# shematic.net
KiCad netlist of a schematic drawn in EAGLE
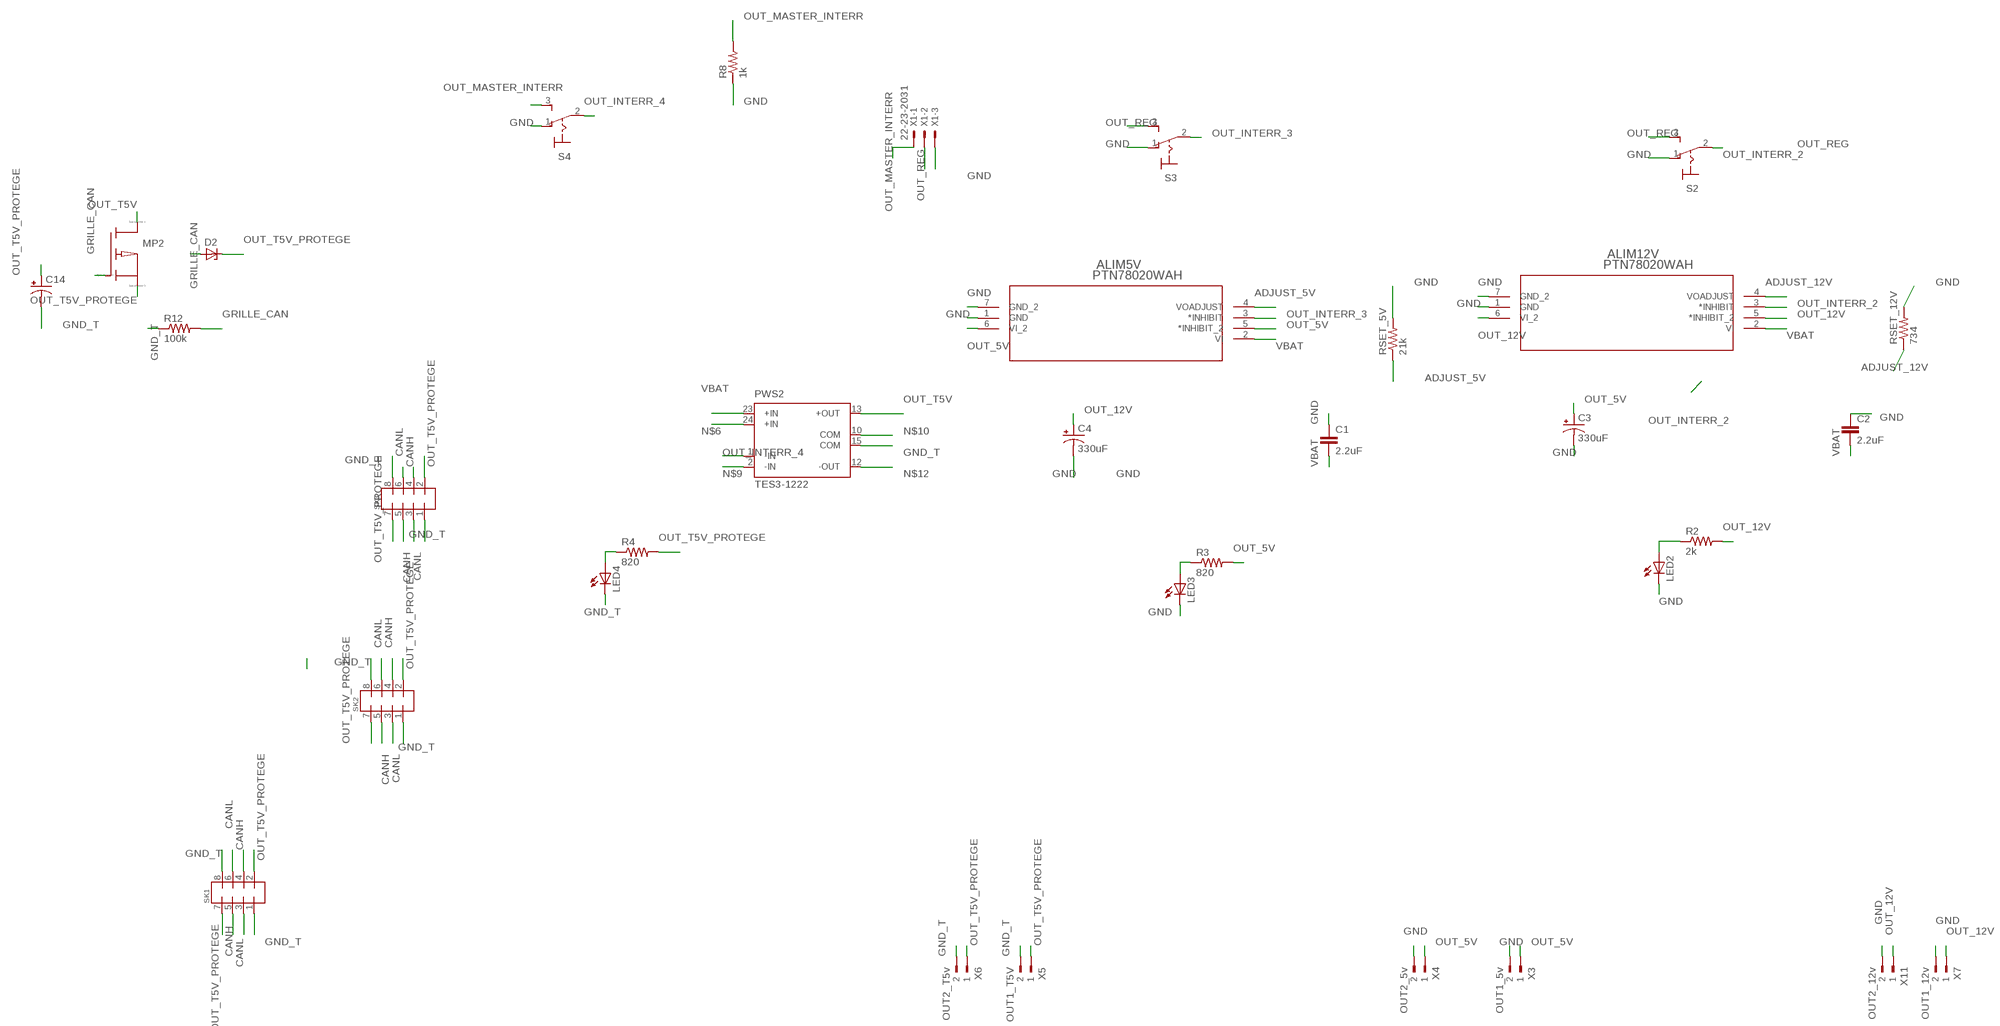
[diagram p0: schematic, sheet 1, part 1 of 2]
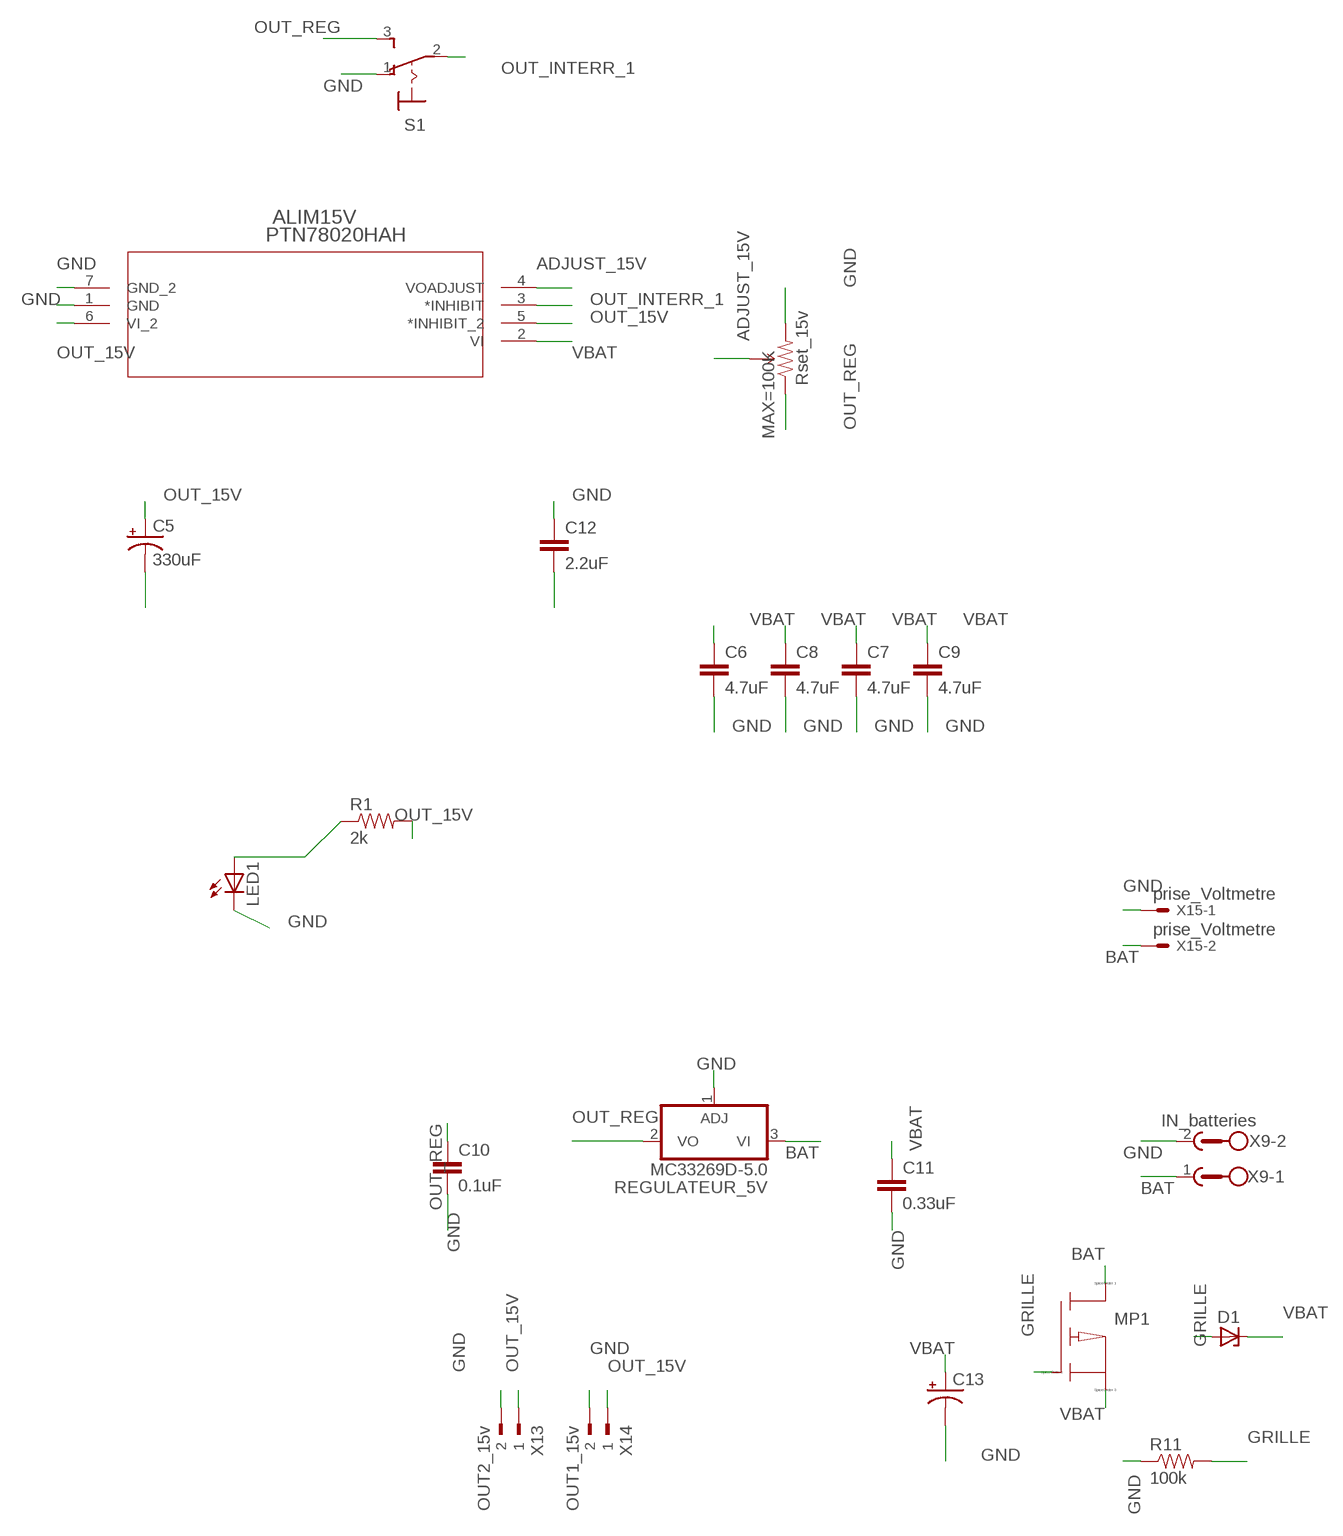
[diagram p1: schematic, sheet 1, part 2 of 2]

(export (version "E")
  (design (tool "Eeschema 10.0.6"))
  (components
    (comp (ref "ALIM5V")
      (value "PTN78020WAH")
      (footprint "eagle-import:EUK7")
      (libsource (lib "eagle-import") (part "PTN78020_"))
    )
    (comp (ref "ALIM12V")
      (value "PTN78020WAH")
      (footprint "eagle-import:EUK7")
      (libsource (lib "eagle-import") (part "PTN78020_"))
    )
    (comp (ref "ALIM15V")
      (value "PTN78020HAH")
      (footprint "eagle-import:EUK7")
      (libsource (lib "eagle-import") (part "PTN78020_"))
    )
    (comp (ref "C1")
      (value "2.2uF")
      (footprint "eagle-import:0805")
      (libsource (lib "eagle-import") (part "CAP0805"))
    )
    (comp (ref "C2")
      (value "2.2uF")
      (footprint "eagle-import:0805")
      (libsource (lib "eagle-import") (part "CAP0805"))
    )
    (comp (ref "C3")
      (value "330uF")
      (footprint "eagle-import:CPOL-RADIAL-100UF-25V")
      (libsource (lib "eagle-import") (part "CAP_POLPTH1"))
    )
    (comp (ref "C4")
      (value "330uF")
      (footprint "eagle-import:CPOL-RADIAL-100UF-25V")
      (libsource (lib "eagle-import") (part "CAP_POLPTH1"))
    )
    (comp (ref "C5")
      (value "330uF")
      (footprint "eagle-import:CPOL-RADIAL-100UF-25V")
      (libsource (lib "eagle-import") (part "CAP_POLPTH1"))
    )
    (comp (ref "C6")
      (value "4.7uF")
      (footprint "eagle-import:0805")
      (libsource (lib "eagle-import") (part "CAP0805"))
    )
    (comp (ref "C7")
      (value "4.7uF")
      (footprint "eagle-import:0805")
      (libsource (lib "eagle-import") (part "CAP0805"))
    )
    (comp (ref "C8")
      (value "4.7uF")
      (footprint "eagle-import:0805")
      (libsource (lib "eagle-import") (part "CAP0805"))
    )
    (comp (ref "C9")
      (value "4.7uF")
      (footprint "eagle-import:0805")
      (libsource (lib "eagle-import") (part "CAP0805"))
    )
    (comp (ref "C10")
      (value "0.1uF")
      (footprint "eagle-import:0805")
      (libsource (lib "eagle-import") (part "CAP0805"))
    )
    (comp (ref "C11")
      (value "0.33uF")
      (footprint "eagle-import:0805")
      (libsource (lib "eagle-import") (part "CAP0805"))
    )
    (comp (ref "C12")
      (value "2.2uF")
      (footprint "eagle-import:0805")
      (libsource (lib "eagle-import") (part "CAP0805"))
    )
    (comp (ref "C13")
      (value "CAP_POLPTH1")
      (footprint "eagle-import:CPOL-RADIAL-100UF-25V")
      (libsource (lib "eagle-import") (part "SparkFun-Passives_CAP_POLPTH1"))
    )
    (comp (ref "C14")
      (value "CAP_POLPTH1")
      (footprint "eagle-import:CPOL-RADIAL-100UF-25V")
      (libsource (lib "eagle-import") (part "SparkFun-Passives_CAP_POLPTH1"))
    )
    (comp (ref "D1")
      (value "ZENER-DIODESOT23")
      (footprint "eagle-import:SOT23")
      (libsource (lib "eagle-import") (part "ZENER-DIODESOT23"))
    )
    (comp (ref "D2")
      (value "ZENER-DIODESOT23")
      (footprint "eagle-import:SOT23")
      (libsource (lib "eagle-import") (part "ZENER-DIODESOT23"))
    )
    (comp (ref "LED1")
      (value "LEDCHIP-LED0805")
      (footprint "eagle-import:CHIP-LED0805")
      (libsource (lib "eagle-import") (part "LEDCHIP-LED0805"))
    )
    (comp (ref "LED2")
      (value "LEDCHIP-LED0805")
      (footprint "eagle-import:CHIP-LED0805")
      (libsource (lib "eagle-import") (part "LEDCHIP-LED0805"))
    )
    (comp (ref "LED3")
      (value "LEDCHIP-LED0805")
      (footprint "eagle-import:CHIP-LED0805")
      (libsource (lib "eagle-import") (part "LEDCHIP-LED0805"))
    )
    (comp (ref "LED4")
      (value "LEDCHIP-LED0805")
      (footprint "eagle-import:CHIP-LED0805")
      (libsource (lib "eagle-import") (part "LEDCHIP-LED0805"))
    )
    (comp (ref "MAX=100K")
      (value "Rset_15v")
      (footprint "eagle-import:3386U")
      (libsource (lib "eagle-import") (part "TRIMPOT-PTH-KNOB"))
    )
    (comp (ref "MP1")
      (value "PMOS")
      (footprint "eagle-import:SOT23")
      (libsource (lib "eagle-import") (part "PMOS"))
    )
    (comp (ref "MP2")
      (value "PMOS")
      (footprint "eagle-import:SOT23")
      (libsource (lib "eagle-import") (part "PMOS"))
    )
    (comp (ref "PWS2")
      (value "TES3-1222")
      (footprint "eagle-import:TES3")
      (libsource (lib "eagle-import") (part "TES3-1222"))
    )
    (comp (ref "R1")
      (value "2k")
      (footprint "eagle-import:0805")
      (libsource (lib "eagle-import") (part "SparkFun-Resistors_RESISTOR0805-RES"))
    )
    (comp (ref "R2")
      (value "2k")
      (footprint "eagle-import:0805")
      (libsource (lib "eagle-import") (part "SparkFun-Resistors_RESISTOR0805-RES"))
    )
    (comp (ref "R3")
      (value "820")
      (footprint "eagle-import:0805")
      (libsource (lib "eagle-import") (part "SparkFun-Resistors_RESISTOR0805-RES"))
    )
    (comp (ref "R4")
      (value "820")
      (footprint "eagle-import:0805")
      (libsource (lib "eagle-import") (part "SparkFun-Resistors_RESISTOR0805-RES"))
    )
    (comp (ref "R8")
      (value "1k")
      (footprint "eagle-import:0805")
      (libsource (lib "eagle-import") (part "SparkFun-Resistors_RESISTOR0805-RES"))
    )
    (comp (ref "R11")
      (value "100k")
      (footprint "eagle-import:0805")
      (libsource (lib "eagle-import") (part "RESISTOR0805-RES"))
    )
    (comp (ref "R12")
      (value "100k")
      (footprint "eagle-import:0805")
      (libsource (lib "eagle-import") (part "RESISTOR0805-RES"))
    )
    (comp (ref "REGULATEUR_5V")
      (value "MC33269D-5.0")
      (footprint "eagle-import:DPACK")
      (libsource (lib "eagle-import") (part "MC33269?D-5.0"))
    )
    (comp (ref "RSET_5V")
      (value "21k")
      (footprint "eagle-import:0805")
      (libsource (lib "eagle-import") (part "RESISTOR0805-RES"))
    )
    (comp (ref "RSET_12V")
      (value "734")
      (footprint "eagle-import:0805")
      (libsource (lib "eagle-import") (part "RESISTOR0805-RES"))
    )
    (comp (ref "S1")
      (value "M9040P")
      (footprint "eagle-import:M9040P")
      (libsource (lib "eagle-import") (part "M9040P"))
    )
    (comp (ref "S2")
      (value "M9040P")
      (footprint "eagle-import:M9040P")
      (libsource (lib "eagle-import") (part "M9040P"))
    )
    (comp (ref "S3")
      (value "M9040P")
      (footprint "eagle-import:M9040P")
      (libsource (lib "eagle-import") (part "M9040P"))
    )
    (comp (ref "S4")
      (value "M9040P")
      (footprint "eagle-import:M9040P")
      (libsource (lib "eagle-import") (part "M9040P"))
    )
    (comp (ref "SK1")
      (value "MMATCH-8-PTH")
      (footprint "eagle-import:AMP-215079-8")
      (libsource (lib "eagle-import") (part "MMATCH-8-PTH"))
    )
    (comp (ref "SK2")
      (value "MMATCH-8-PTH")
      (footprint "eagle-import:AMP-215079-8")
      (libsource (lib "eagle-import") (part "MMATCH-8-PTH"))
    )
    (comp (ref "SK3")
      (value "MMATCH-8-PTH")
      (footprint "eagle-import:AMP-215079-8")
      (libsource (lib "eagle-import") (part "MMATCH-8-PTH"))
    )
    (comp (ref "X1")
      (value "22-23-2031")
      (footprint "eagle-import:22-23-2031")
      (fields (field (name "MF") "MOLEX"))
      (libsource (lib "eagle-import") (part "22-23-2031"))
    )
    (comp (ref "X3")
      (value "OUT1_5v")
      (footprint "eagle-import:90-2")
      (libsource (lib "eagle-import") (part "90-2"))
    )
    (comp (ref "X4")
      (value "OUT2_5v")
      (footprint "eagle-import:90-2")
      (libsource (lib "eagle-import") (part "90-2"))
    )
    (comp (ref "X5")
      (value "OUT1_T5V")
      (footprint "eagle-import:90-2")
      (libsource (lib "eagle-import") (part "90-2"))
    )
    (comp (ref "X6")
      (value "OUT2_T5v")
      (footprint "eagle-import:90-2")
      (libsource (lib "eagle-import") (part "90-2"))
    )
    (comp (ref "X7")
      (value "OUT1_12v")
      (footprint "eagle-import:90-2")
      (libsource (lib "eagle-import") (part "90-2"))
    )
    (comp (ref "X9")
      (value "IN_batteries")
      (footprint "eagle-import:GMSTBA2")
      (fields (field (name "MF") "FARNELL") (field (name "MPN") "1757242"))
      (libsource (lib "eagle-import") (part "GMSTBA2"))
    )
    (comp (ref "X11")
      (value "OUT2_12v")
      (footprint "eagle-import:90-2")
      (libsource (lib "eagle-import") (part "90-2"))
    )
    (comp (ref "X13")
      (value "OUT2_15v")
      (footprint "eagle-import:90-2")
      (libsource (lib "eagle-import") (part "90-2"))
    )
    (comp (ref "X14")
      (value "OUT1_15v")
      (footprint "eagle-import:90-2")
      (libsource (lib "eagle-import") (part "90-2"))
    )
    (comp (ref "X15")
      (value "prise_Voltmetre")
      (footprint "eagle-import:KK-156-2")
      (libsource (lib "eagle-import") (part "KK-156-2"))
    )
  )
  (nets
    (net (code "1") (name "/ADJUST_5V") (class "Default")
      (node (ref "ALIM5V") (pin "4") (pinfunction "VOADJUST_4") (pintype "passive"))
      (node (ref "RSET_5V") (pin "1") (pinfunction "1_1") (pintype "passive"))
    )
    (net (code "2") (name "/ADJUST_12V") (class "Default")
      (node (ref "ALIM12V") (pin "4") (pinfunction "VOADJUST_4") (pintype "passive"))
      (node (ref "RSET_12V") (pin "1") (pinfunction "1_1") (pintype "passive"))
    )
    (net (code "3") (name "/ADJUST_15V") (class "Default")
      (node (ref "ALIM15V") (pin "4") (pinfunction "VOADJUST_4") (pintype "passive"))
      (node (ref "MAX=100K") (pin "2") (pinfunction "WIPER_2") (pintype "passive"))
    )
    (net (code "4") (name "/BAT") (class "Default")
      (node (ref "MP1") (pin "3") (pinfunction "D_3") (pintype "passive"))
      (node (ref "REGULATEUR_5V") (pin "3") (pinfunction "VI_3") (pintype "input"))
      (node (ref "X15") (pin "2") (pinfunction "S_2") (pintype "passive"))
      (node (ref "X9") (pin "1") (pinfunction "1_1") (pintype "passive"))
    )
    (net (code "5") (name "/CANH") (class "Default")
      (node (ref "SK1") (pin "4") (pinfunction "4_4") (pintype "bidirectional"))
      (node (ref "SK1") (pin "5") (pinfunction "5_5") (pintype "bidirectional"))
      (node (ref "SK2") (pin "4") (pinfunction "4_4") (pintype "bidirectional"))
      (node (ref "SK2") (pin "5") (pinfunction "5_5") (pintype "bidirectional"))
      (node (ref "SK3") (pin "4") (pinfunction "4_4") (pintype "bidirectional"))
      (node (ref "SK3") (pin "5") (pinfunction "5_5") (pintype "bidirectional"))
    )
    (net (code "6") (name "/CANL") (class "Default")
      (node (ref "SK1") (pin "3") (pinfunction "3_3") (pintype "bidirectional"))
      (node (ref "SK1") (pin "6") (pinfunction "6_6") (pintype "bidirectional"))
      (node (ref "SK2") (pin "3") (pinfunction "3_3") (pintype "bidirectional"))
      (node (ref "SK2") (pin "6") (pinfunction "6_6") (pintype "bidirectional"))
      (node (ref "SK3") (pin "3") (pinfunction "3_3") (pintype "bidirectional"))
      (node (ref "SK3") (pin "6") (pinfunction "6_6") (pintype "bidirectional"))
    )
    (net (code "7") (name "/GND") (class "Default")
      (node (ref "ALIM12V") (pin "1") (pinfunction "GND_1") (pintype "passive"))
      (node (ref "ALIM12V") (pin "7") (pinfunction "GND_2_7") (pintype "passive"))
      (node (ref "ALIM15V") (pin "1") (pinfunction "GND_1") (pintype "passive"))
      (node (ref "ALIM15V") (pin "7") (pinfunction "GND_2_7") (pintype "passive"))
      (node (ref "ALIM5V") (pin "1") (pinfunction "GND_1") (pintype "passive"))
      (node (ref "ALIM5V") (pin "7") (pinfunction "GND_2_7") (pintype "passive"))
      (node (ref "C1") (pin "1") (pinfunction "1_1") (pintype "passive"))
      (node (ref "C10") (pin "2") (pinfunction "2_2") (pintype "passive"))
      (node (ref "C11") (pin "2") (pinfunction "2_2") (pintype "passive"))
      (node (ref "C12") (pin "1") (pinfunction "1_1") (pintype "passive"))
      (node (ref "C13") (pin "2") (pinfunction "-_2") (pintype "passive"))
      (node (ref "C2") (pin "1") (pinfunction "1_1") (pintype "passive"))
      (node (ref "C3") (pin "2") (pinfunction "-_2") (pintype "passive"))
      (node (ref "C4") (pin "2") (pinfunction "-_2") (pintype "passive"))
      (node (ref "C5") (pin "2") (pinfunction "-_2") (pintype "passive"))
      (node (ref "C6") (pin "2") (pinfunction "2_2") (pintype "passive"))
      (node (ref "C7") (pin "2") (pinfunction "2_2") (pintype "passive"))
      (node (ref "C8") (pin "2") (pinfunction "2_2") (pintype "passive"))
      (node (ref "C9") (pin "2") (pinfunction "2_2") (pintype "passive"))
      (node (ref "LED1") (pin "C") (pinfunction "C_C") (pintype "passive"))
      (node (ref "LED2") (pin "C") (pinfunction "C_C") (pintype "passive"))
      (node (ref "LED3") (pin "C") (pinfunction "C_C") (pintype "passive"))
      (node (ref "MAX=100K") (pin "3") (pinfunction "CW_3") (pintype "passive"))
      (node (ref "R11") (pin "1") (pinfunction "1_1") (pintype "passive"))
      (node (ref "R8") (pin "1") (pinfunction "1_1") (pintype "passive"))
      (node (ref "REGULATEUR_5V") (pin "1") (pinfunction "ADJ_1") (pintype "input"))
      (node (ref "RSET_12V") (pin "2") (pinfunction "2_2") (pintype "passive"))
      (node (ref "RSET_5V") (pin "2") (pinfunction "2_2") (pintype "passive"))
      (node (ref "S1") (pin "1") (pinfunction "O_1") (pintype "passive"))
      (node (ref "S2") (pin "1") (pinfunction "O_1") (pintype "passive"))
      (node (ref "S3") (pin "1") (pinfunction "O_1") (pintype "passive"))
      (node (ref "S4") (pin "1") (pinfunction "O_1") (pintype "passive"))
      (node (ref "X1") (pin "3") (pinfunction "S_3") (pintype "passive"))
      (node (ref "X11") (pin "2") (pinfunction "2_2") (pintype "passive"))
      (node (ref "X13") (pin "2") (pinfunction "2_2") (pintype "passive"))
      (node (ref "X14") (pin "2") (pinfunction "2_2") (pintype "passive"))
      (node (ref "X15") (pin "1") (pinfunction "S_1") (pintype "passive"))
      (node (ref "X3") (pin "2") (pinfunction "2_2") (pintype "passive"))
      (node (ref "X4") (pin "2") (pinfunction "2_2") (pintype "passive"))
      (node (ref "X7") (pin "2") (pinfunction "2_2") (pintype "passive"))
      (node (ref "X9") (pin "2") (pinfunction "1_2") (pintype "passive"))
    )
    (net (code "8") (name "/GND_T") (class "Default")
      (node (ref "C14") (pin "2") (pinfunction "-_2") (pintype "passive"))
      (node (ref "LED4") (pin "C") (pinfunction "C_C") (pintype "passive"))
      (node (ref "PWS2") (pin "15") (pinfunction "COM_15") (pintype "passive"))
      (node (ref "R12") (pin "1") (pinfunction "1_1") (pintype "passive"))
      (node (ref "SK1") (pin "1") (pinfunction "1_1") (pintype "bidirectional"))
      (node (ref "SK1") (pin "8") (pinfunction "8_8") (pintype "bidirectional"))
      (node (ref "SK2") (pin "1") (pinfunction "1_1") (pintype "bidirectional"))
      (node (ref "SK2") (pin "8") (pinfunction "8_8") (pintype "bidirectional"))
      (node (ref "SK3") (pin "1") (pinfunction "1_1") (pintype "bidirectional"))
      (node (ref "SK3") (pin "8") (pinfunction "8_8") (pintype "bidirectional"))
      (node (ref "X5") (pin "2") (pinfunction "2_2") (pintype "passive"))
      (node (ref "X6") (pin "2") (pinfunction "2_2") (pintype "passive"))
    )
    (net (code "9") (name "/GRILLE") (class "Default")
      (node (ref "D1") (pin "1") (pinfunction "A_1") (pintype "passive"))
      (node (ref "MP1") (pin "1") (pinfunction "G_1") (pintype "passive"))
      (node (ref "R11") (pin "2") (pinfunction "2_2") (pintype "passive"))
    )
    (net (code "10") (name "/GRILLE_CAN") (class "Default")
      (node (ref "D2") (pin "1") (pinfunction "A_1") (pintype "passive"))
      (node (ref "MP2") (pin "1") (pinfunction "G_1") (pintype "passive"))
      (node (ref "R12") (pin "2") (pinfunction "2_2") (pintype "passive"))
    )
    (net (code "11") (name "/N$6") (class "Default")
      (node (ref "PWS2") (pin "24") (pinfunction "+IN_24") (pintype "input"))
    )
    (net (code "12") (name "/N$9") (class "Default")
      (node (ref "PWS2") (pin "2") (pinfunction "-IN_2") (pintype "input"))
    )
    (net (code "13") (name "/N$10") (class "Default")
      (node (ref "PWS2") (pin "10") (pinfunction "COM_10") (pintype "passive"))
    )
    (net (code "14") (name "/N$12") (class "Default")
      (node (ref "PWS2") (pin "12") (pinfunction "-OUT_12") (pintype "output"))
    )
    (net (code "15") (name "/OUT_5V") (class "Default")
      (node (ref "ALIM5V") (pin "5") (pinfunction "*INHIBIT_2_5") (pintype "passive"))
      (node (ref "ALIM5V") (pin "6") (pinfunction "VI_2_6") (pintype "passive"))
      (node (ref "C3") (pin "1") (pinfunction "+_1") (pintype "passive"))
      (node (ref "R3") (pin "2") (pinfunction "2_2") (pintype "passive"))
      (node (ref "X3") (pin "1") (pinfunction "1_1") (pintype "passive"))
      (node (ref "X4") (pin "1") (pinfunction "1_1") (pintype "passive"))
    )
    (net (code "16") (name "/OUT_12V") (class "Default")
      (node (ref "ALIM12V") (pin "5") (pinfunction "*INHIBIT_2_5") (pintype "passive"))
      (node (ref "ALIM12V") (pin "6") (pinfunction "VI_2_6") (pintype "passive"))
      (node (ref "C4") (pin "1") (pinfunction "+_1") (pintype "passive"))
      (node (ref "R2") (pin "2") (pinfunction "2_2") (pintype "passive"))
      (node (ref "X11") (pin "1") (pinfunction "1_1") (pintype "passive"))
      (node (ref "X7") (pin "1") (pinfunction "1_1") (pintype "passive"))
    )
    (net (code "17") (name "/OUT_15V") (class "Default")
      (node (ref "ALIM15V") (pin "5") (pinfunction "*INHIBIT_2_5") (pintype "passive"))
      (node (ref "ALIM15V") (pin "6") (pinfunction "VI_2_6") (pintype "passive"))
      (node (ref "C5") (pin "1") (pinfunction "+_1") (pintype "passive"))
      (node (ref "R1") (pin "2") (pinfunction "2_2") (pintype "passive"))
      (node (ref "X13") (pin "1") (pinfunction "1_1") (pintype "passive"))
      (node (ref "X14") (pin "1") (pinfunction "1_1") (pintype "passive"))
    )
    (net (code "18") (name "/OUT_INTERR_1") (class "Default")
      (node (ref "ALIM15V") (pin "3") (pinfunction "*INHIBIT_3") (pintype "passive"))
      (node (ref "S1") (pin "2") (pinfunction "P_2") (pintype "passive"))
    )
    (net (code "19") (name "/OUT_INTERR_2") (class "Default")
      (node (ref "ALIM12V") (pin "3") (pinfunction "*INHIBIT_3") (pintype "passive"))
      (node (ref "S2") (pin "2") (pinfunction "P_2") (pintype "passive"))
    )
    (net (code "20") (name "/OUT_INTERR_3") (class "Default")
      (node (ref "ALIM5V") (pin "3") (pinfunction "*INHIBIT_3") (pintype "passive"))
      (node (ref "S3") (pin "2") (pinfunction "P_2") (pintype "passive"))
    )
    (net (code "21") (name "/OUT_INTERR_4") (class "Default")
      (node (ref "PWS2") (pin "1") (pinfunction "-IN_1") (pintype "input"))
      (node (ref "S4") (pin "2") (pinfunction "P_2") (pintype "passive"))
    )
    (net (code "22") (name "/OUT_MASTER_INTERR") (class "Default")
      (node (ref "R8") (pin "2") (pinfunction "2_2") (pintype "passive"))
      (node (ref "S4") (pin "3") (pinfunction "S_3") (pintype "passive"))
      (node (ref "X1") (pin "1") (pinfunction "S_1") (pintype "passive"))
    )
    (net (code "23") (name "/OUT_REG") (class "Default")
      (node (ref "C10") (pin "1") (pinfunction "1_1") (pintype "passive"))
      (node (ref "MAX=100K") (pin "1") (pinfunction "CCW_1") (pintype "passive"))
      (node (ref "REGULATEUR_5V") (pin "2") (pinfunction "VO_2") (pintype "passive"))
      (node (ref "S1") (pin "3") (pinfunction "S_3") (pintype "passive"))
      (node (ref "S2") (pin "3") (pinfunction "S_3") (pintype "passive"))
      (node (ref "S3") (pin "3") (pinfunction "S_3") (pintype "passive"))
      (node (ref "X1") (pin "2") (pinfunction "S_2") (pintype "passive"))
    )
    (net (code "24") (name "/OUT_T5V") (class "Default")
      (node (ref "MP2") (pin "3") (pinfunction "D_3") (pintype "passive"))
      (node (ref "PWS2") (pin "13") (pinfunction "+OUT_13") (pintype "output"))
    )
    (net (code "25") (name "/OUT_T5V_PROTEGE") (class "Default")
      (node (ref "C14") (pin "1") (pinfunction "+_1") (pintype "passive"))
      (node (ref "D2") (pin "3") (pinfunction "C_3") (pintype "passive"))
      (node (ref "MP2") (pin "2") (pinfunction "S_2") (pintype "passive"))
      (node (ref "R4") (pin "2") (pinfunction "2_2") (pintype "passive"))
      (node (ref "SK1") (pin "2") (pinfunction "2_2") (pintype "bidirectional"))
      (node (ref "SK1") (pin "7") (pinfunction "7_7") (pintype "bidirectional"))
      (node (ref "SK2") (pin "2") (pinfunction "2_2") (pintype "bidirectional"))
      (node (ref "SK2") (pin "7") (pinfunction "7_7") (pintype "bidirectional"))
      (node (ref "SK3") (pin "2") (pinfunction "2_2") (pintype "bidirectional"))
      (node (ref "SK3") (pin "7") (pinfunction "7_7") (pintype "bidirectional"))
      (node (ref "X5") (pin "1") (pinfunction "1_1") (pintype "passive"))
      (node (ref "X6") (pin "1") (pinfunction "1_1") (pintype "passive"))
    )
    (net (code "26") (name "/VBAT") (class "Default")
      (node (ref "ALIM12V") (pin "2") (pinfunction "VI_2") (pintype "passive"))
      (node (ref "ALIM15V") (pin "2") (pinfunction "VI_2") (pintype "passive"))
      (node (ref "ALIM5V") (pin "2") (pinfunction "VI_2") (pintype "passive"))
      (node (ref "C1") (pin "2") (pinfunction "2_2") (pintype "passive"))
      (node (ref "C11") (pin "1") (pinfunction "1_1") (pintype "passive"))
      (node (ref "C12") (pin "2") (pinfunction "2_2") (pintype "passive"))
      (node (ref "C13") (pin "1") (pinfunction "+_1") (pintype "passive"))
      (node (ref "C2") (pin "2") (pinfunction "2_2") (pintype "passive"))
      (node (ref "C6") (pin "1") (pinfunction "1_1") (pintype "passive"))
      (node (ref "C7") (pin "1") (pinfunction "1_1") (pintype "passive"))
      (node (ref "C8") (pin "1") (pinfunction "1_1") (pintype "passive"))
      (node (ref "C9") (pin "1") (pinfunction "1_1") (pintype "passive"))
      (node (ref "D1") (pin "3") (pinfunction "C_3") (pintype "passive"))
      (node (ref "MP1") (pin "2") (pinfunction "S_2") (pintype "passive"))
      (node (ref "PWS2") (pin "23") (pinfunction "+IN_23") (pintype "input"))
    )
    (net (code "27") (name "Net-(LED1-PadA)") (class "Default")
      (node (ref "LED1") (pin "A") (pinfunction "A_A") (pintype "passive"))
      (node (ref "R1") (pin "1") (pinfunction "1_1") (pintype "passive"))
    )
    (net (code "28") (name "Net-(LED2-PadA)") (class "Default")
      (node (ref "LED2") (pin "A") (pinfunction "A_A") (pintype "passive"))
      (node (ref "R2") (pin "1") (pinfunction "1_1") (pintype "passive"))
    )
    (net (code "29") (name "Net-(LED3-PadA)") (class "Default")
      (node (ref "LED3") (pin "A") (pinfunction "A_A") (pintype "passive"))
      (node (ref "R3") (pin "1") (pinfunction "1_1") (pintype "passive"))
    )
    (net (code "30") (name "Net-(LED4-PadA)") (class "Default")
      (node (ref "LED4") (pin "A") (pinfunction "A_A") (pintype "passive"))
      (node (ref "R4") (pin "1") (pinfunction "1_1") (pintype "passive"))
    )
  )
)
